# Analog_Front_End.net
KiCad netlist of a schematic drawn in Altium Designer
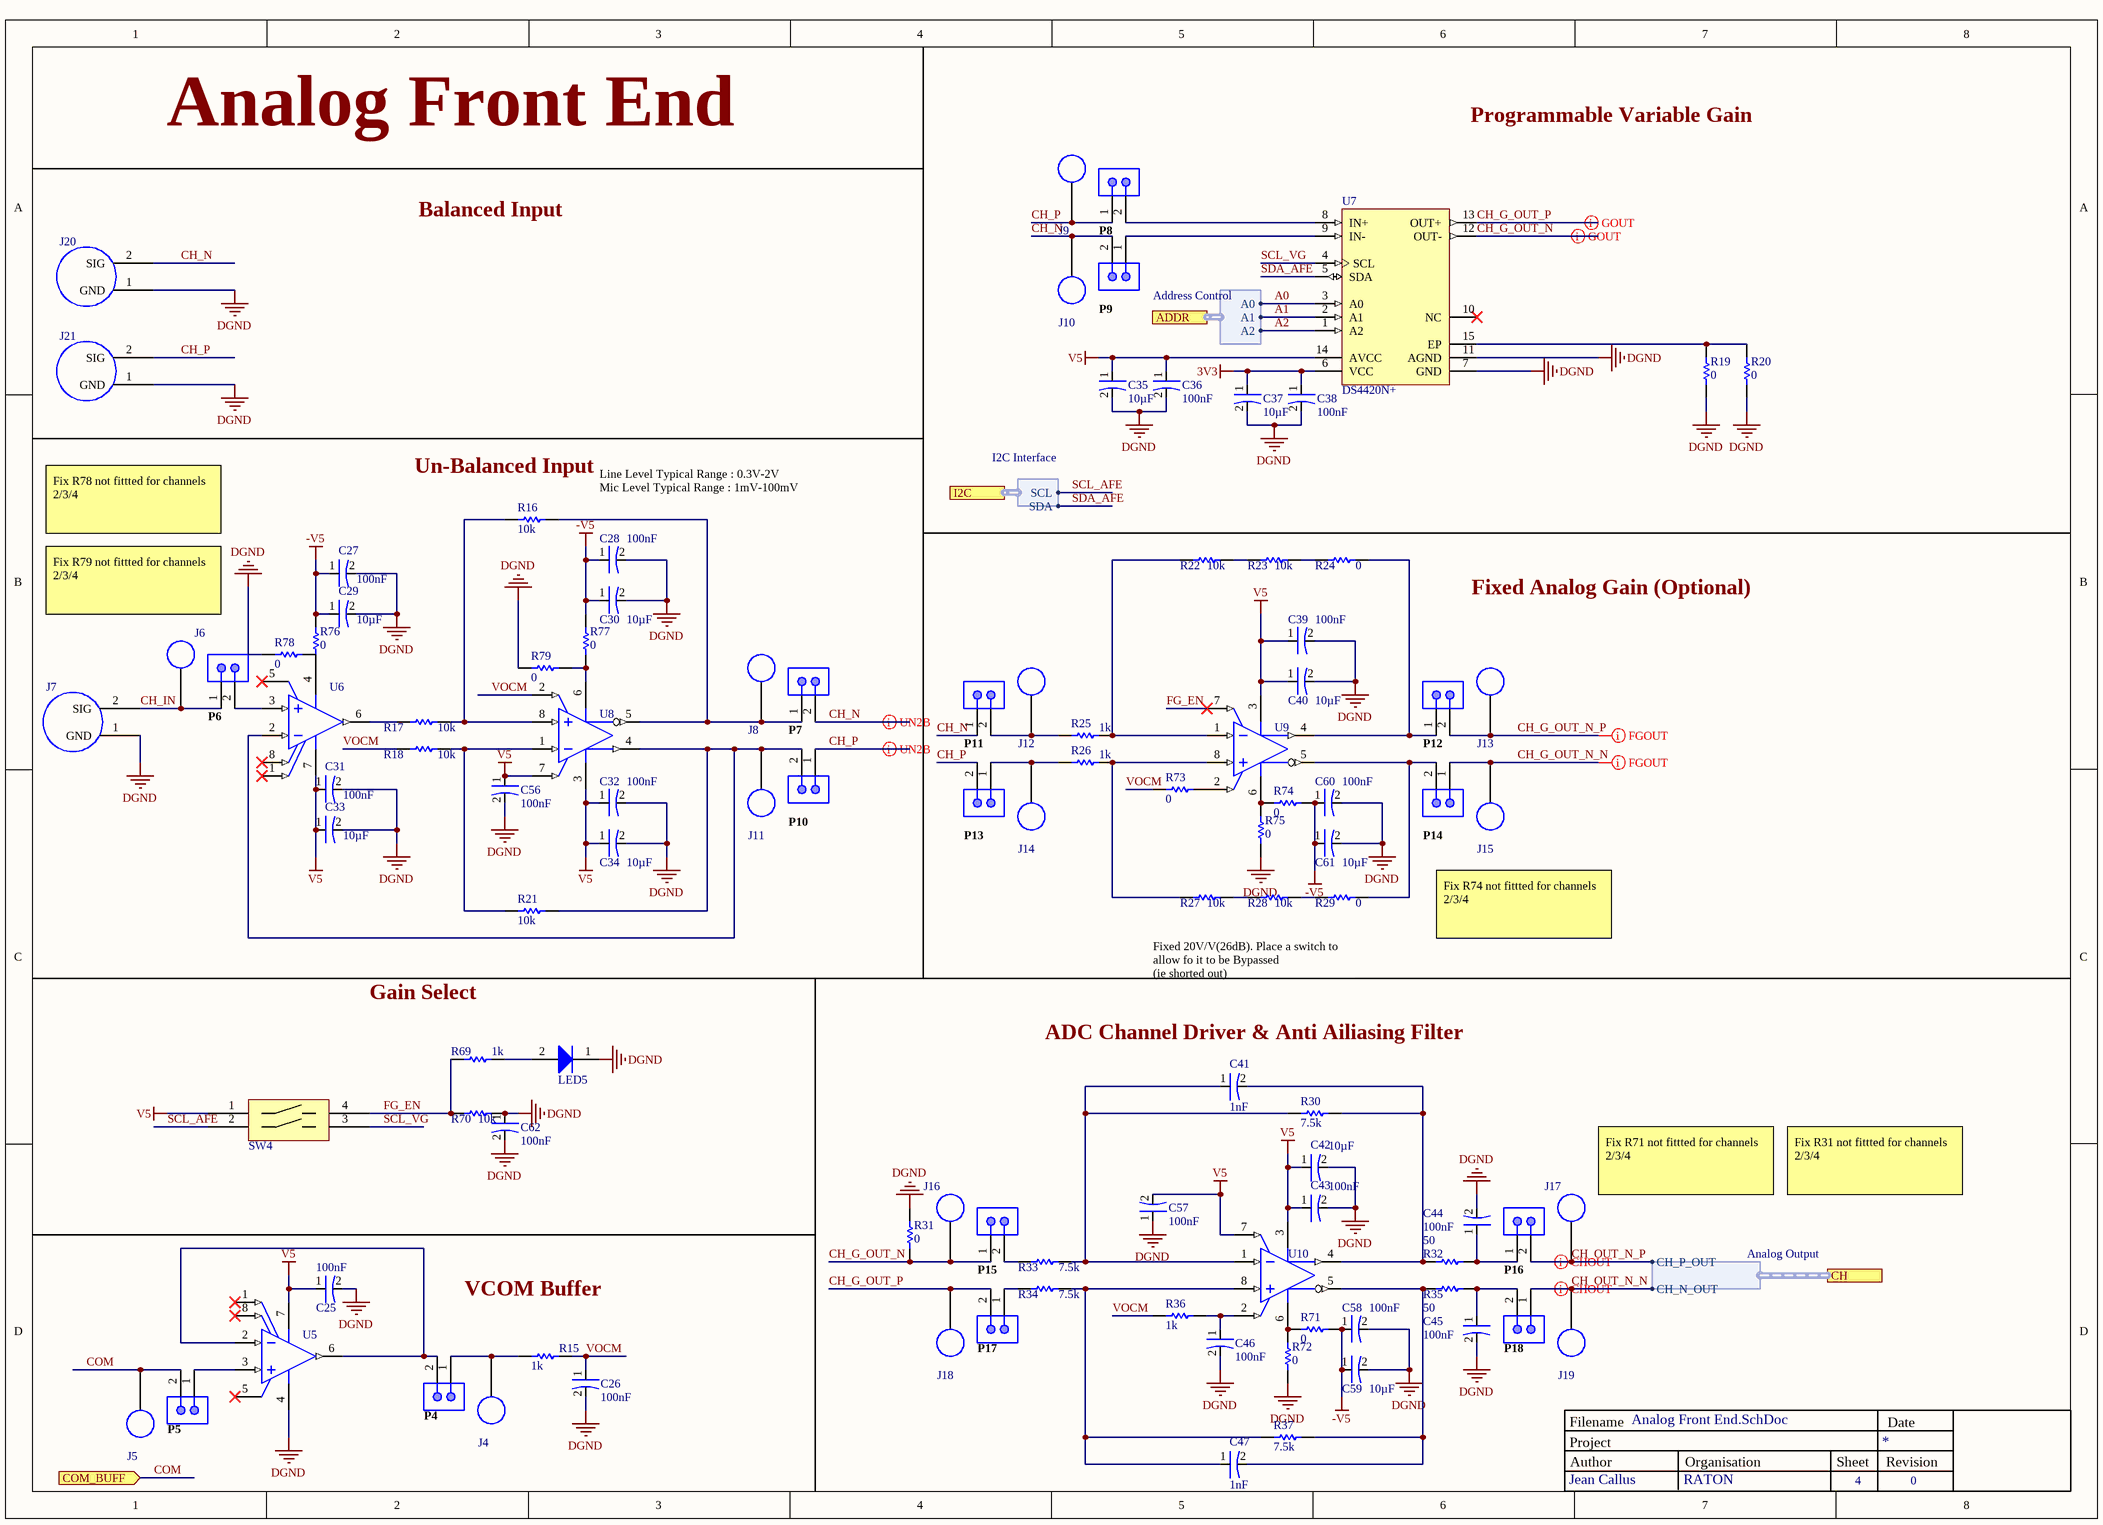
[diagram p0: Analog Front End.SchDoc]

(export (version "E")
  (design (tool "Eeschema 10.0.6"))
  (components
    (comp (ref "C25")
      (value "100nF")
      (footprint "0805-M")
      (description "CAP-0.1uF-CER-0805-50V- X7R-5%")
      (fields
        (field (name "MANUFACTURER") "Generic")
        (field (name "Comment") "CAP 0.1uF CER 0805 50V  X7R 5%")
      )
      (libsource (lib "") (part "Symbol_1"))
    )
    (comp (ref "C26")
      (value "100nF")
      (footprint "0805-M")
      (description "CAP-0.1uF-CER-0805-50V- X7R-5%")
      (fields
        (field (name "MANUFACTURER") "Generic")
        (field (name "Comment") "CAP 0.1uF CER 0805 50V  X7R 5%")
      )
      (libsource (lib "") (part "Symbol_1"))
    )
    (comp (ref "C27")
      (value "100nF")
      (footprint "0805-M")
      (description "CAP-0.1uF-CER-0805-50V- X7R-5%")
      (fields
        (field (name "MANUFACTURER") "Generic")
        (field (name "Comment") "CAP 0.1uF CER 0805 50V  X7R 5%")
      )
      (libsource (lib "") (part "Symbol_2"))
    )
    (comp (ref "C28")
      (value "100nF")
      (footprint "0805-M")
      (description "CAP-0.1uF-CER-0805-50V- X7R-5%")
      (fields
        (field (name "MANUFACTURER") "Generic")
        (field (name "Comment") "CAP 0.1uF CER 0805 50V  X7R 5%")
      )
      (libsource (lib "") (part "Symbol_2"))
    )
    (comp (ref "C29")
      (value "10µF")
      (footprint "0805-M")
      (description "CAP-10uF-CER-0805-25V-X5R-10%")
      (fields
        (field (name "MANUFACTURER") "Generic")
        (field (name "Comment") "CAP 10uF CER 0805 25V X5R 10%")
      )
      (libsource (lib "") (part "Symbol_2"))
    )
    (comp (ref "C30")
      (value "10µF")
      (footprint "0805-M")
      (description "CAP-10uF-CER-0805-25V-X5R-10%")
      (fields
        (field (name "MANUFACTURER") "Generic")
        (field (name "Comment") "CAP 10uF CER 0805 25V X5R 10%")
      )
      (libsource (lib "") (part "Symbol_2"))
    )
    (comp (ref "C31")
      (value "100nF")
      (footprint "0805-M")
      (description "CAP-0.1uF-CER-0805-50V- X7R-5%")
      (fields
        (field (name "MANUFACTURER") "Generic")
        (field (name "Comment") "CAP 0.1uF CER 0805 50V  X7R 5%")
      )
      (libsource (lib "") (part "Symbol_2"))
    )
    (comp (ref "C32")
      (value "100nF")
      (footprint "0805-M")
      (description "CAP-0.1uF-CER-0805-50V- X7R-5%")
      (fields
        (field (name "MANUFACTURER") "Generic")
        (field (name "Comment") "CAP 0.1uF CER 0805 50V  X7R 5%")
      )
      (libsource (lib "") (part "Symbol_2"))
    )
    (comp (ref "C33")
      (value "10µF")
      (footprint "0805-M")
      (description "CAP-10uF-CER-0805-25V-X5R-10%")
      (fields
        (field (name "MANUFACTURER") "Generic")
        (field (name "Comment") "CAP 10uF CER 0805 25V X5R 10%")
      )
      (libsource (lib "") (part "Symbol_2"))
    )
    (comp (ref "C34")
      (value "10µF")
      (footprint "0805-M")
      (description "CAP-10uF-CER-0805-25V-X5R-10%")
      (fields
        (field (name "MANUFACTURER") "Generic")
        (field (name "Comment") "CAP 10uF CER 0805 25V X5R 10%")
      )
      (libsource (lib "") (part "Symbol_2"))
    )
    (comp (ref "C35")
      (value "10µF")
      (footprint "0805-M")
      (description "CAP-10uF-CER-0805-25V-X5R-10%")
      (fields
        (field (name "MANUFACTURER") "Generic")
        (field (name "Comment") "CAP 10uF CER 0805 25V X5R 10%")
      )
      (libsource (lib "") (part "Symbol_2"))
    )
    (comp (ref "C36")
      (value "100nF")
      (footprint "0805-M")
      (description "CAP-0.1uF-CER-0805-50V- X7R-5%")
      (fields
        (field (name "MANUFACTURER") "Generic")
        (field (name "Comment") "CAP 0.1uF CER 0805 50V  X7R 5%")
      )
      (libsource (lib "") (part "Symbol_2"))
    )
    (comp (ref "C37")
      (value "10µF")
      (footprint "0805-M")
      (description "CAP-10uF-CER-0805-25V-X5R-10%")
      (fields
        (field (name "MANUFACTURER") "Generic")
        (field (name "Comment") "CAP 10uF CER 0805 25V X5R 10%")
      )
      (libsource (lib "") (part "Symbol_2"))
    )
    (comp (ref "C38")
      (value "100nF")
      (footprint "0805-M")
      (description "CAP-0.1uF-CER-0805-50V- X7R-5%")
      (fields
        (field (name "MANUFACTURER") "Generic")
        (field (name "Comment") "CAP 0.1uF CER 0805 50V  X7R 5%")
      )
      (libsource (lib "") (part "Symbol_2"))
    )
    (comp (ref "C39")
      (value "100nF")
      (footprint "0805-M")
      (description "CAP-0.1uF-CER-0805-50V- X7R-5%")
      (fields
        (field (name "MANUFACTURER") "Generic")
        (field (name "Comment") "CAP 0.1uF CER 0805 50V  X7R 5%")
      )
      (libsource (lib "") (part "Symbol_2"))
    )
    (comp (ref "C40")
      (value "10µF")
      (footprint "0805-M")
      (description "CAP-10uF-CER-0805-25V-X5R-10%")
      (fields
        (field (name "MANUFACTURER") "Generic")
        (field (name "Comment") "CAP 10uF CER 0805 25V X5R 10%")
      )
      (libsource (lib "") (part "Symbol_2"))
    )
    (comp (ref "C41")
      (value "1nF")
      (footprint "0805-M")
      (description "CAP 1nF CER 0805 25V X7R 5%")
      (fields (field (name "MANUFACTURER") "Generic"))
      (libsource (lib "") (part "Symbol_1"))
    )
    (comp (ref "C42")
      (value "10µF")
      (footprint "0805-M")
      (description "CAP-10uF-CER-0805-25V-X5R-10%")
      (fields
        (field (name "MANUFACTURER") "Generic")
        (field (name "Comment") "CAP 10uF CER 0805 25V X5R 10%")
      )
      (libsource (lib "") (part "Symbol_1"))
    )
    (comp (ref "C43")
      (value "100nF")
      (footprint "0805-M")
      (description "CAP-0.1uF-CER-0805-50V- X7R-5%")
      (fields
        (field (name "MANUFACTURER") "Generic")
        (field (name "Comment") "CAP 0.1uF CER 0805 50V  X7R 5%")
      )
      (libsource (lib "") (part "Symbol_1"))
    )
    (comp (ref "C44")
      (value "100nF")
      (footprint "0805-M")
      (description "CAP-0.1uF-CER-0805-50V- X7R-5%")
      (fields
        (field (name "MANUFACTURER") "Generic")
        (field (name "Comment") "CAP 0.1uF CER 0805 50V  X7R 5%")
      )
      (libsource (lib "") (part "Symbol_1"))
    )
    (comp (ref "C45")
      (value "100nF")
      (footprint "0805-M")
      (description "CAP-0.1uF-CER-0805-50V- X7R-5%")
      (fields
        (field (name "MANUFACTURER") "Generic")
        (field (name "Comment") "CAP 0.1uF CER 0805 50V  X7R 5%")
      )
      (libsource (lib "") (part "Symbol_1"))
    )
    (comp (ref "C46")
      (value "100nF")
      (footprint "0805-M")
      (description "CAP-0.1uF-CER-0805-50V- X7R-5%")
      (fields
        (field (name "MANUFACTURER") "Generic")
        (field (name "Comment") "CAP 0.1uF CER 0805 50V  X7R 5%")
      )
      (libsource (lib "") (part "Symbol_1"))
    )
    (comp (ref "C47")
      (value "1nF")
      (footprint "0805-M")
      (description "CAP 1nF CER 0805 25V X7R 5%")
      (fields (field (name "MANUFACTURER") "Generic"))
      (libsource (lib "") (part "Symbol_1"))
    )
    (comp (ref "C56")
      (value "100nF")
      (footprint "0805-M")
      (description "CAP-0.1uF-CER-0805-50V- X7R-5%")
      (fields
        (field (name "MANUFACTURER") "Generic")
        (field (name "Comment") "CAP 0.1uF CER 0805 50V  X7R 5%")
      )
      (libsource (lib "") (part "Symbol_2"))
    )
    (comp (ref "C57")
      (value "100nF")
      (footprint "0805-M")
      (description "CAP-0.1uF-CER-0805-50V- X7R-5%")
      (fields
        (field (name "MANUFACTURER") "Generic")
        (field (name "Comment") "CAP 0.1uF CER 0805 50V  X7R 5%")
      )
      (libsource (lib "") (part "Symbol_1"))
    )
    (comp (ref "C58")
      (value "100nF")
      (footprint "0805-M")
      (description "CAP-0.1uF-CER-0805-50V- X7R-5%")
      (fields
        (field (name "MANUFACTURER") "Generic")
        (field (name "Comment") "CAP 0.1uF CER 0805 50V  X7R 5%")
      )
      (libsource (lib "") (part "Symbol_2"))
    )
    (comp (ref "C59")
      (value "10µF")
      (footprint "0805-M")
      (description "CAP-10uF-CER-0805-25V-X5R-10%")
      (fields
        (field (name "MANUFACTURER") "Generic")
        (field (name "Comment") "CAP 10uF CER 0805 25V X5R 10%")
      )
      (libsource (lib "") (part "Symbol_2"))
    )
    (comp (ref "C60")
      (value "100nF")
      (footprint "0805-M")
      (description "CAP-0.1uF-CER-0805-50V- X7R-5%")
      (fields
        (field (name "MANUFACTURER") "Generic")
        (field (name "Comment") "CAP 0.1uF CER 0805 50V  X7R 5%")
      )
      (libsource (lib "") (part "Symbol_2"))
    )
    (comp (ref "C61")
      (value "10µF")
      (footprint "0805-M")
      (description "CAP-10uF-CER-0805-25V-X5R-10%")
      (fields
        (field (name "MANUFACTURER") "Generic")
        (field (name "Comment") "CAP 10uF CER 0805 25V X5R 10%")
      )
      (libsource (lib "") (part "Symbol_2"))
    )
    (comp (ref "C62")
      (value "100nF")
      (footprint "0805-M")
      (description "CAP-0.1uF-CER-0805-50V- X7R-5%")
      (fields
        (field (name "MANUFACTURER") "Generic")
        (field (name "Comment") "CAP 0.1uF CER 0805 50V  X7R 5%")
      )
      (libsource (lib "") (part "Symbol_2"))
    )
    (comp (ref "J4")
      (value "151-203-RC")
      (footprint "151-203-RC-Footprint-1")
      (description "PCB-Probe-Ring")
      (libsource (lib "University of Malta - MEMENTO") (part "PCB Probe Ring"))
    )
    (comp (ref "J5")
      (value "151-203-RC")
      (footprint "151-203-RC-Footprint-1")
      (description "PCB-Probe-Ring")
      (libsource (lib "University of Malta - MEMENTO") (part "PCB Probe Ring"))
    )
    (comp (ref "J6")
      (value "151-203-RC")
      (footprint "151-203-RC-Footprint-1")
      (description "PCB-Probe-Ring")
      (libsource (lib "University of Malta - MEMENTO") (part "PCB Probe Ring"))
    )
    (comp (ref "J7")
      (value "SMA CONNECTOR")
      (footprint "SMA CONNECTOR-Footprint-1")
      (fields (field (name "MANUFACTURER") "LPRS"))
      (libsource (lib "University of Malta - MEMENTO") (part "SMA CONNECTOR"))
    )
    (comp (ref "J8")
      (value "151-203-RC")
      (footprint "151-203-RC-Footprint-1")
      (description "PCB-Probe-Ring")
      (libsource (lib "University of Malta - MEMENTO") (part "PCB Probe Ring"))
    )
    (comp (ref "J9")
      (value "151-203-RC")
      (footprint "151-203-RC-Footprint-1")
      (description "PCB-Probe-Ring")
      (libsource (lib "University of Malta - MEMENTO") (part "PCB Probe Ring"))
    )
    (comp (ref "J10")
      (value "151-203-RC")
      (footprint "151-203-RC-Footprint-1")
      (description "PCB-Probe-Ring")
      (libsource (lib "University of Malta - MEMENTO") (part "PCB Probe Ring"))
    )
    (comp (ref "J11")
      (value "151-203-RC")
      (footprint "151-203-RC-Footprint-1")
      (description "PCB-Probe-Ring")
      (libsource (lib "University of Malta - MEMENTO") (part "PCB Probe Ring"))
    )
    (comp (ref "J12")
      (value "151-203-RC")
      (footprint "151-203-RC-Footprint-1")
      (description "PCB-Probe-Ring")
      (libsource (lib "University of Malta - MEMENTO") (part "PCB Probe Ring"))
    )
    (comp (ref "J13")
      (value "151-203-RC")
      (footprint "151-203-RC-Footprint-1")
      (description "PCB-Probe-Ring")
      (libsource (lib "University of Malta - MEMENTO") (part "PCB Probe Ring"))
    )
    (comp (ref "J14")
      (value "151-203-RC")
      (footprint "151-203-RC-Footprint-1")
      (description "PCB-Probe-Ring")
      (libsource (lib "University of Malta - MEMENTO") (part "PCB Probe Ring"))
    )
    (comp (ref "J15")
      (value "151-203-RC")
      (footprint "151-203-RC-Footprint-1")
      (description "PCB-Probe-Ring")
      (libsource (lib "University of Malta - MEMENTO") (part "PCB Probe Ring"))
    )
    (comp (ref "J16")
      (value "151-203-RC")
      (footprint "151-203-RC-Footprint-1")
      (description "PCB-Probe-Ring")
      (libsource (lib "University of Malta - MEMENTO") (part "PCB Probe Ring"))
    )
    (comp (ref "J17")
      (value "151-203-RC")
      (footprint "151-203-RC-Footprint-1")
      (description "PCB-Probe-Ring")
      (libsource (lib "University of Malta - MEMENTO") (part "PCB Probe Ring"))
    )
    (comp (ref "J18")
      (value "151-203-RC")
      (footprint "151-203-RC-Footprint-1")
      (description "PCB-Probe-Ring")
      (libsource (lib "University of Malta - MEMENTO") (part "PCB Probe Ring"))
    )
    (comp (ref "J19")
      (value "151-203-RC")
      (footprint "151-203-RC-Footprint-1")
      (description "PCB-Probe-Ring")
      (libsource (lib "University of Malta - MEMENTO") (part "PCB Probe Ring"))
    )
    (comp (ref "J20")
      (value "SMA CONNECTOR")
      (footprint "SMA CONNECTOR-Footprint-1")
      (fields (field (name "MANUFACTURER") "LPRS"))
      (libsource (lib "University of Malta - MEMENTO") (part "SMA CONNECTOR"))
    )
    (comp (ref "J21")
      (value "SMA CONNECTOR")
      (footprint "SMA CONNECTOR-Footprint-1")
      (fields (field (name "MANUFACTURER") "LPRS"))
      (libsource (lib "University of Malta - MEMENTO") (part "SMA CONNECTOR"))
    )
    (comp (ref "LED5")
      (value "LED 0603 Red 20mA 1.7V")
      (footprint "0603 Generic")
      (description "LED-0603-Red-20mA-1.7V-STOCK")
      (fields (field (name "MANUFACTURER") "Generic"))
      (libsource (lib "") (part "Symbol_3"))
    )
    (comp (ref "P4")
      (value "GENERIC 2PIN HEADER MALE")
      (footprint "GENERIC 2PIN HEADER 0")
      (description "CONN MAL TH 2 0Deg HEADER")
      (fields (field (name "MANUFACTURER") "Generic"))
      (libsource (lib "University of Malta - MEMENTO") (part "GENERIC 2PIN HEADER MALE"))
    )
    (comp (ref "P5")
      (value "GENERIC 2PIN HEADER MALE")
      (footprint "GENERIC 2PIN HEADER 0")
      (description "CONN MAL TH 2 0Deg HEADER")
      (fields (field (name "MANUFACTURER") "Generic"))
      (libsource (lib "University of Malta - MEMENTO") (part "GENERIC 2PIN HEADER MALE"))
    )
    (comp (ref "P6")
      (value "GENERIC 2PIN HEADER MALE")
      (footprint "GENERIC 2PIN HEADER 0")
      (description "CONN MAL TH 2 0Deg HEADER")
      (fields (field (name "MANUFACTURER") "Generic"))
      (libsource (lib "") (part "GENERIC 2PIN HEADER MALE_1"))
    )
    (comp (ref "P7")
      (value "GENERIC 2PIN HEADER MALE")
      (footprint "GENERIC 2PIN HEADER 0")
      (description "CONN MAL TH 2 0Deg HEADER")
      (fields (field (name "MANUFACTURER") "Generic"))
      (libsource (lib "") (part "GENERIC 2PIN HEADER MALE_1"))
    )
    (comp (ref "P8")
      (value "GENERIC 2PIN HEADER MALE")
      (footprint "GENERIC 2PIN HEADER 0")
      (description "CONN MAL TH 2 0Deg HEADER")
      (fields (field (name "MANUFACTURER") "Generic"))
      (libsource (lib "") (part "GENERIC 2PIN HEADER MALE_1"))
    )
    (comp (ref "P9")
      (value "GENERIC 2PIN HEADER MALE")
      (footprint "GENERIC 2PIN HEADER 0")
      (description "CONN MAL TH 2 0Deg HEADER")
      (fields (field (name "MANUFACTURER") "Generic"))
      (libsource (lib "University of Malta - MEMENTO") (part "GENERIC 2PIN HEADER MALE"))
    )
    (comp (ref "P10")
      (value "GENERIC 2PIN HEADER MALE")
      (footprint "GENERIC 2PIN HEADER 0")
      (description "CONN MAL TH 2 0Deg HEADER")
      (fields (field (name "MANUFACTURER") "Generic"))
      (libsource (lib "University of Malta - MEMENTO") (part "GENERIC 2PIN HEADER MALE"))
    )
    (comp (ref "P11")
      (value "GENERIC 2PIN HEADER MALE")
      (footprint "GENERIC 2PIN HEADER 0")
      (description "CONN MAL TH 2 0Deg HEADER")
      (fields (field (name "MANUFACTURER") "Generic"))
      (libsource (lib "") (part "GENERIC 2PIN HEADER MALE_1"))
    )
    (comp (ref "P12")
      (value "GENERIC 2PIN HEADER MALE")
      (footprint "GENERIC 2PIN HEADER 0")
      (description "CONN MAL TH 2 0Deg HEADER")
      (fields (field (name "MANUFACTURER") "Generic"))
      (libsource (lib "") (part "GENERIC 2PIN HEADER MALE_1"))
    )
    (comp (ref "P13")
      (value "GENERIC 2PIN HEADER MALE")
      (footprint "GENERIC 2PIN HEADER 0")
      (description "CONN MAL TH 2 0Deg HEADER")
      (fields (field (name "MANUFACTURER") "Generic"))
      (libsource (lib "University of Malta - MEMENTO") (part "GENERIC 2PIN HEADER MALE"))
    )
    (comp (ref "P14")
      (value "GENERIC 2PIN HEADER MALE")
      (footprint "GENERIC 2PIN HEADER 0")
      (description "CONN MAL TH 2 0Deg HEADER")
      (fields (field (name "MANUFACTURER") "Generic"))
      (libsource (lib "University of Malta - MEMENTO") (part "GENERIC 2PIN HEADER MALE"))
    )
    (comp (ref "P15")
      (value "GENERIC 2PIN HEADER MALE")
      (footprint "GENERIC 2PIN HEADER 0")
      (description "CONN MAL TH 2 0Deg HEADER")
      (fields (field (name "MANUFACTURER") "Generic"))
      (libsource (lib "") (part "GENERIC 2PIN HEADER MALE_1"))
    )
    (comp (ref "P16")
      (value "GENERIC 2PIN HEADER MALE")
      (footprint "GENERIC 2PIN HEADER 0")
      (description "CONN MAL TH 2 0Deg HEADER")
      (fields (field (name "MANUFACTURER") "Generic"))
      (libsource (lib "") (part "GENERIC 2PIN HEADER MALE_1"))
    )
    (comp (ref "P17")
      (value "GENERIC 2PIN HEADER MALE")
      (footprint "GENERIC 2PIN HEADER 0")
      (description "CONN MAL TH 2 0Deg HEADER")
      (fields (field (name "MANUFACTURER") "Generic"))
      (libsource (lib "University of Malta - MEMENTO") (part "GENERIC 2PIN HEADER MALE"))
    )
    (comp (ref "P18")
      (value "GENERIC 2PIN HEADER MALE")
      (footprint "GENERIC 2PIN HEADER 0")
      (description "CONN MAL TH 2 0Deg HEADER")
      (fields (field (name "MANUFACTURER") "Generic"))
      (libsource (lib "University of Malta - MEMENTO") (part "GENERIC 2PIN HEADER MALE"))
    )
    (comp (ref "R15")
      (value "1k")
      (footprint "0805-M")
      (description "RES-1k-0805-125mW-5%")
      (fields (field (name "MANUFACTURER") "Generic") (field (name "Comment") "RES 1k 0805 125mW 5%"))
      (libsource (lib "University of Malta - MEMENTO") (part "Symbol"))
    )
    (comp (ref "R16")
      (value "10k")
      (footprint "0402-M")
      (description "RES-10k-0402-63mW-5%")
      (fields (field (name "MANUFACTURER") "Generic") (field (name "Comment") "RES 10k 0402 63mW 5%"))
      (libsource (lib "University of Malta - MEMENTO") (part "Symbol"))
    )
    (comp (ref "R17")
      (value "10k")
      (footprint "0402-M")
      (description "RES-10k-0402-63mW-5%")
      (fields (field (name "MANUFACTURER") "Generic") (field (name "Comment") "RES 10k 0402 63mW 5%"))
      (libsource (lib "University of Malta - MEMENTO") (part "Symbol"))
    )
    (comp (ref "R18")
      (value "10k")
      (footprint "0402-M")
      (description "RES-10k-0402-63mW-5%")
      (fields (field (name "MANUFACTURER") "Generic") (field (name "Comment") "RES 10k 0402 63mW 5%"))
      (libsource (lib "University of Malta - MEMENTO") (part "Symbol"))
    )
    (comp (ref "R19")
      (value "0")
      (footprint "0402-M")
      (description "RES-0-0402-63mW-5%")
      (fields (field (name "MANUFACTURER") "Generic") (field (name "Comment") "RES 0 0402 63mW"))
      (libsource (lib "University of Malta - MEMENTO") (part "Symbol"))
    )
    (comp (ref "R20")
      (value "0")
      (footprint "0402-M")
      (description "RES-0-0402-63mW-5%")
      (fields (field (name "MANUFACTURER") "Generic") (field (name "Comment") "RES 0 0402 63mW"))
      (libsource (lib "University of Malta - MEMENTO") (part "Symbol"))
    )
    (comp (ref "R21")
      (value "10k")
      (footprint "0402-M")
      (description "RES-10k-0402-63mW-5%")
      (fields (field (name "MANUFACTURER") "Generic") (field (name "Comment") "RES 10k 0402 63mW 5%"))
      (libsource (lib "University of Malta - MEMENTO") (part "Symbol"))
    )
    (comp (ref "R22")
      (value "10k")
      (footprint "0805-M")
      (description "RES-10k-0805-125mW-1%")
      (fields (field (name "MANUFACTURER") "Generic") (field (name "Comment") "RES 10k 0805 125mW 1%"))
      (libsource (lib "University of Malta - MEMENTO") (part "Symbol"))
    )
    (comp (ref "R23")
      (value "10k")
      (footprint "0805-M")
      (description "RES-10k-0805-125mW-1%")
      (fields (field (name "MANUFACTURER") "Generic") (field (name "Comment") "RES 10k 0805 125mW 1%"))
      (libsource (lib "University of Malta - MEMENTO") (part "Symbol"))
    )
    (comp (ref "R24")
      (value "0")
      (footprint "0402-M")
      (description "RES-0-0402-63mW-5%")
      (fields (field (name "MANUFACTURER") "Generic") (field (name "Comment") "RES 0 0402 63mW"))
      (libsource (lib "University of Malta - MEMENTO") (part "Symbol"))
    )
    (comp (ref "R25")
      (value "1k")
      (footprint "0805-M")
      (description "RES-1k-0805-125mW-5%")
      (fields (field (name "MANUFACTURER") "Generic") (field (name "Comment") "RES 1k 0805 125mW 5%"))
      (libsource (lib "University of Malta - MEMENTO") (part "Symbol"))
    )
    (comp (ref "R26")
      (value "1k")
      (footprint "0805-M")
      (description "RES-1k-0805-125mW-5%")
      (fields (field (name "MANUFACTURER") "Generic") (field (name "Comment") "RES 1k 0805 125mW 5%"))
      (libsource (lib "University of Malta - MEMENTO") (part "Symbol"))
    )
    (comp (ref "R27")
      (value "10k")
      (footprint "0805-M")
      (description "RES-10k-0805-125mW-1%")
      (fields (field (name "MANUFACTURER") "Generic") (field (name "Comment") "RES 10k 0805 125mW 1%"))
      (libsource (lib "University of Malta - MEMENTO") (part "Symbol"))
    )
    (comp (ref "R28")
      (value "10k")
      (footprint "0805-M")
      (description "RES-10k-0805-125mW-1%")
      (fields (field (name "MANUFACTURER") "Generic") (field (name "Comment") "RES 10k 0805 125mW 1%"))
      (libsource (lib "University of Malta - MEMENTO") (part "Symbol"))
    )
    (comp (ref "R29")
      (value "0")
      (footprint "0402-M")
      (description "RES-0-0402-63mW-5%")
      (fields (field (name "MANUFACTURER") "Generic") (field (name "Comment") "RES 0 0402 63mW"))
      (libsource (lib "University of Malta - MEMENTO") (part "Symbol"))
    )
    (comp (ref "R30")
      (value "7.5k")
      (footprint "0402-M")
      (description "RES-7.5k-0402-63mW-5%")
      (fields (field (name "MANUFACTURER") "Generic") (field (name "Comment") "RES 7.5k 0402 63mW 5%"))
      (libsource (lib "University of Malta - MEMENTO") (part "Symbol"))
    )
    (comp (ref "R31")
      (value "0")
      (footprint "0402-M")
      (description "RES-0-0402-63mW-5%")
      (fields (field (name "MANUFACTURER") "Generic") (field (name "Comment") "RES 0 0402 63mW"))
      (libsource (lib "University of Malta - MEMENTO") (part "Symbol"))
    )
    (comp (ref "R32")
      (value "50")
      (footprint "0805-L")
      (description "RES-50-0805-125mW-1%")
      (fields (field (name "MANUFACTURER") "Generic") (field (name "Comment") "RES 50 0805 125mW 1%"))
      (libsource (lib "University of Malta - MEMENTO") (part "Symbol"))
    )
    (comp (ref "R33")
      (value "7.5k")
      (footprint "0402-M")
      (description "RES-7.5k-0402-63mW-5%")
      (fields (field (name "MANUFACTURER") "Generic") (field (name "Comment") "RES 7.5k 0402 63mW 5%"))
      (libsource (lib "University of Malta - MEMENTO") (part "Symbol"))
    )
    (comp (ref "R34")
      (value "7.5k")
      (footprint "0402-M")
      (description "RES-7.5k-0402-63mW-5%")
      (fields (field (name "MANUFACTURER") "Generic") (field (name "Comment") "RES 7.5k 0402 63mW 5%"))
      (libsource (lib "University of Malta - MEMENTO") (part "Symbol"))
    )
    (comp (ref "R35")
      (value "50")
      (footprint "0805-L")
      (description "RES-50-0805-125mW-1%")
      (fields (field (name "MANUFACTURER") "Generic") (field (name "Comment") "RES 50 0805 125mW 1%"))
      (libsource (lib "University of Malta - MEMENTO") (part "Symbol"))
    )
    (comp (ref "R36")
      (value "1k")
      (footprint "0805-M")
      (description "RES-1k-0805-125mW-5%")
      (fields (field (name "MANUFACTURER") "Generic") (field (name "Comment") "RES 1k 0805 125mW 5%"))
      (libsource (lib "University of Malta - MEMENTO") (part "Symbol"))
    )
    (comp (ref "R37")
      (value "7.5k")
      (footprint "0402-M")
      (description "RES-7.5k-0402-63mW-5%")
      (fields (field (name "MANUFACTURER") "Generic") (field (name "Comment") "RES 7.5k 0402 63mW 5%"))
      (libsource (lib "University of Malta - MEMENTO") (part "Symbol"))
    )
    (comp (ref "R69")
      (value "1k")
      (footprint "0805-M")
      (description "RES-1k-0805-125mW-5%")
      (fields (field (name "MANUFACTURER") "Generic") (field (name "Comment") "RES 1k 0805 125mW 5%"))
      (libsource (lib "University of Malta - MEMENTO") (part "Symbol"))
    )
    (comp (ref "R70")
      (value "10k")
      (footprint "0805-M")
      (description "RES-10k-0805-125mW-1%")
      (fields (field (name "MANUFACTURER") "Generic") (field (name "Comment") "RES 10k 0805 125mW 1%"))
      (libsource (lib "University of Malta - MEMENTO") (part "Symbol"))
    )
    (comp (ref "R71")
      (value "0")
      (footprint "0402-M")
      (description "RES-0-0402-63mW-5%")
      (fields (field (name "MANUFACTURER") "Generic") (field (name "Comment") "RES 0 0402 63mW"))
      (libsource (lib "University of Malta - MEMENTO") (part "Symbol"))
    )
    (comp (ref "R72")
      (value "0")
      (footprint "0402-M")
      (description "RES-0-0402-63mW-5%")
      (fields (field (name "MANUFACTURER") "Generic") (field (name "Comment") "RES 0 0402 63mW"))
      (libsource (lib "University of Malta - MEMENTO") (part "Symbol"))
    )
    (comp (ref "R73")
      (value "0")
      (footprint "0402-M")
      (description "RES-0-0402-63mW-5%")
      (fields (field (name "MANUFACTURER") "Generic") (field (name "Comment") "RES 0 0402 63mW"))
      (libsource (lib "University of Malta - MEMENTO") (part "Symbol"))
    )
    (comp (ref "R74")
      (value "0")
      (footprint "0402-M")
      (description "RES-0-0402-63mW-5%")
      (fields (field (name "MANUFACTURER") "Generic") (field (name "Comment") "RES 0 0402 63mW"))
      (libsource (lib "University of Malta - MEMENTO") (part "Symbol"))
    )
    (comp (ref "R75")
      (value "0")
      (footprint "0402-M")
      (description "RES-0-0402-63mW-5%")
      (fields (field (name "MANUFACTURER") "Generic") (field (name "Comment") "RES 0 0402 63mW"))
      (libsource (lib "University of Malta - MEMENTO") (part "Symbol"))
    )
    (comp (ref "R76")
      (value "0")
      (footprint "0402-M")
      (description "RES-0-0402-63mW-5%")
      (fields (field (name "MANUFACTURER") "Generic") (field (name "Comment") "RES 0 0402 63mW"))
      (libsource (lib "University of Malta - MEMENTO") (part "Symbol"))
    )
    (comp (ref "R77")
      (value "0")
      (footprint "0402-M")
      (description "RES-0-0402-63mW-5%")
      (fields (field (name "MANUFACTURER") "Generic") (field (name "Comment") "RES 0 0402 63mW"))
      (libsource (lib "University of Malta - MEMENTO") (part "Symbol"))
    )
    (comp (ref "R78")
      (value "0")
      (footprint "0402-M")
      (description "RES-0-0402-63mW-5%")
      (fields (field (name "MANUFACTURER") "Generic") (field (name "Comment") "RES 0 0402 63mW"))
      (libsource (lib "University of Malta - MEMENTO") (part "Symbol"))
    )
    (comp (ref "R79")
      (value "0")
      (footprint "0402-M")
      (description "RES-0-0402-63mW-5%")
      (fields (field (name "MANUFACTURER") "Generic") (field (name "Comment") "RES 0 0402 63mW"))
      (libsource (lib "University of Malta - MEMENTO") (part "Symbol"))
    )
    (comp (ref "SW4")
      (value "210-2MS")
      (footprint "210-2MS-Footprint-1")
      (description "SWITCH DIP SPST 2 100mA 50V")
      (libsource (lib "University of Malta - MEMENTO") (part "210-2MS"))
    )
    (comp (ref "U5")
      (value "OPA227UA/2K5")
      (footprint "D0008A_L")
      (description "IC OPAMP GP 8MHZ 8SOIC")
      (libsource (lib "University of Malta - MEMENTO") (part "TI-OPA227-8"))
    )
    (comp (ref "U6")
      (value "OPA227UA/2K5")
      (footprint "D0008A_L")
      (description "IC OPAMP GP 8MHZ 8SOIC")
      (libsource (lib "University of Malta - MEMENTO") (part "TI-OPA227-8"))
    )
    (comp (ref "U7")
      (value "DS4420N+")
      (footprint "QFN50P400X300X75_HS-15N")
      (description "Maxim DS4420N+, Programmable Gain Amplifier 67dB, 14-Pin TDFN")
      (libsource (lib "University of Malta - MEMENTO") (part "DS4420-T1433+1"))
    )
    (comp (ref "U8")
      (value "OPA1632DR")
      (footprint "D0008A_L")
      (description "IC OPAMP AUDIO 180MHZ 8SOIC")
      (libsource (lib "University of Malta - MEMENTO") (part "TI-OPA1632D8"))
    )
    (comp (ref "U9")
      (value "OPA1632DR")
      (footprint "D0008A_L")
      (description "IC OPAMP AUDIO 180MHZ 8SOIC")
      (libsource (lib "University of Malta - MEMENTO") (part "TI-OPA1632D8"))
    )
    (comp (ref "U10")
      (value "OPA1632DR")
      (footprint "D0008A_L")
      (description "IC OPAMP AUDIO 180MHZ 8SOIC")
      (libsource (lib "University of Malta - MEMENTO") (part "TI-OPA1632D8"))
    )
  )
  (nets
    (net (code "7") (name "-V5") (class "Default")
      (node (ref "C27") (pin "1") (pinfunction "Anode_1") (pintype "passive"))
      (node (ref "C28") (pin "1") (pinfunction "Anode_1") (pintype "passive"))
      (node (ref "C29") (pin "1") (pinfunction "Anode_1") (pintype "passive"))
      (node (ref "C30") (pin "1") (pinfunction "Anode_1") (pintype "passive"))
      (node (ref "C58") (pin "1") (pinfunction "Anode_1") (pintype "passive"))
      (node (ref "C59") (pin "1") (pinfunction "Anode_1") (pintype "passive"))
      (node (ref "C60") (pin "1") (pinfunction "Anode_1") (pintype "passive"))
      (node (ref "C61") (pin "1") (pinfunction "Anode_1") (pintype "passive"))
      (node (ref "R71") (pin "2") (pinfunction "2_2") (pintype "passive"))
      (node (ref "R74") (pin "1") (pinfunction "1_1") (pintype "passive"))
      (node (ref "R76") (pin "1") (pinfunction "1_1") (pintype "passive"))
      (node (ref "R77") (pin "2") (pinfunction "2_2") (pintype "passive"))
    )
    (net (code "8") (name "/A0") (class "Default")
      (node (ref "U7") (pin "3") (pinfunction "A0_3") (pintype "input"))
    )
    (net (code "9") (name "/A1") (class "Default")
      (node (ref "U7") (pin "2") (pinfunction "A1_2") (pintype "input"))
    )
    (net (code "10") (name "/A2") (class "Default")
      (node (ref "U7") (pin "1") (pinfunction "A2_1") (pintype "input"))
    )
    (net (code "11") (name "/CH_G_OUT_N") (class "Default")
      (node (ref "J16") (pin "1") (pinfunction "1_1") (pintype "passive"))
      (node (ref "P15") (pin "1") (pinfunction "1_1") (pintype "passive"))
      (node (ref "R31") (pin "2") (pinfunction "2_2") (pintype "passive"))
      (node (ref "U7") (pin "12") (pinfunction "OUT-_12") (pintype "output"))
    )
    (net (code "12") (name "/CH_G_OUT_N_N") (class "Default")
      (node (ref "J15") (pin "1") (pinfunction "1_1") (pintype "passive"))
      (node (ref "P14") (pin "1") (pinfunction "1_1") (pintype "passive"))
    )
    (net (code "13") (name "/CH_G_OUT_N_P") (class "Default")
      (node (ref "J13") (pin "1") (pinfunction "1_1") (pintype "passive"))
      (node (ref "P12") (pin "2") (pinfunction "2_2") (pintype "passive"))
    )
    (net (code "14") (name "/CH_G_OUT_P") (class "Default")
      (node (ref "J18") (pin "1") (pinfunction "1_1") (pintype "passive"))
      (node (ref "P17") (pin "2") (pinfunction "2_2") (pintype "passive"))
      (node (ref "U7") (pin "13") (pinfunction "OUT+_13") (pintype "output"))
    )
    (net (code "15") (name "/CH_IN") (class "Default")
      (node (ref "J6") (pin "1") (pinfunction "1_1") (pintype "passive"))
      (node (ref "J7") (pin "2") (pinfunction "SIG_2") (pintype "passive"))
      (node (ref "P6") (pin "1") (pinfunction "1_1") (pintype "passive"))
    )
    (net (code "16") (name "/CH_N") (class "Default")
      (node (ref "J10") (pin "1") (pinfunction "1_1") (pintype "passive"))
      (node (ref "J20") (pin "2") (pinfunction "SIG_2") (pintype "passive"))
      (node (ref "P11") (pin "1") (pinfunction "1_1") (pintype "passive"))
      (node (ref "P7") (pin "2") (pinfunction "2_2") (pintype "passive"))
      (node (ref "P9") (pin "2") (pinfunction "2_2") (pintype "passive"))
    )
    (net (code "17") (name "/CH_OUT_N_N") (class "Default")
      (node (ref "J19") (pin "1") (pinfunction "1_1") (pintype "passive"))
      (node (ref "P18") (pin "1") (pinfunction "1_1") (pintype "passive"))
    )
    (net (code "18") (name "/CH_OUT_N_P") (class "Default")
      (node (ref "J17") (pin "1") (pinfunction "1_1") (pintype "passive"))
      (node (ref "P16") (pin "2") (pinfunction "2_2") (pintype "passive"))
    )
    (net (code "19") (name "/CH_P") (class "Default")
      (node (ref "J21") (pin "2") (pinfunction "SIG_2") (pintype "passive"))
      (node (ref "J9") (pin "1") (pinfunction "1_1") (pintype "passive"))
      (node (ref "P10") (pin "1") (pinfunction "1_1") (pintype "passive"))
      (node (ref "P13") (pin "2") (pinfunction "2_2") (pintype "passive"))
      (node (ref "P8") (pin "1") (pinfunction "1_1") (pintype "passive"))
    )
    (net (code "20") (name "/COM") (class "Default")
      (node (ref "J5") (pin "1") (pinfunction "1_1") (pintype "passive"))
      (node (ref "P5") (pin "2") (pinfunction "2_2") (pintype "passive"))
    )
    (net (code "21") (name "/FG_EN") (class "Default")
      (node (ref "R69") (pin "1") (pinfunction "1_1") (pintype "passive"))
      (node (ref "R70") (pin "1") (pinfunction "1_1") (pintype "passive"))
      (node (ref "SW4") (pin "4") (pinfunction "4_4") (pintype "passive"))
      (node (ref "U9") (pin "7") (pinfunction "ENABLE_7") (pintype "input"))
    )
    (net (code "22") (name "/SCL_AFE") (class "Default")
      (node (ref "SW4") (pin "2") (pinfunction "2_2") (pintype "passive"))
    )
    (net (code "23") (name "/SCL_VG") (class "Default")
      (node (ref "SW4") (pin "3") (pinfunction "4_3") (pintype "passive"))
      (node (ref "U7") (pin "4") (pinfunction "SCL_4") (pintype "input"))
    )
    (net (code "24") (name "/SDA_AFE") (class "Default")
      (node (ref "U7") (pin "5") (pinfunction "SDA_5") (pintype "bidirectional"))
    )
    (net (code "25") (name "/VOCM") (class "Default")
      (node (ref "C26") (pin "1") (pinfunction "Anode_1") (pintype "passive"))
      (node (ref "R15") (pin "2") (pinfunction "2_2") (pintype "passive"))
      (node (ref "R18") (pin "1") (pinfunction "1_1") (pintype "passive"))
      (node (ref "R36") (pin "1") (pinfunction "1_1") (pintype "passive"))
      (node (ref "R73") (pin "2") (pinfunction "2_2") (pintype "passive"))
      (node (ref "U8") (pin "2") (pinfunction "VOCM_2") (pintype "input"))
    )
    (net (code "29") (name "3V3") (class "Default")
      (node (ref "C37") (pin "1") (pinfunction "Anode_1") (pintype "passive"))
      (node (ref "C38") (pin "1") (pinfunction "Anode_1") (pintype "passive"))
      (node (ref "U7") (pin "6") (pinfunction "VCC_6") (pintype "power_in"))
    )
    (net (code "30") (name "DGND") (class "Default")
      (node (ref "C25") (pin "2") (pinfunction "Cathode_2") (pintype "passive"))
      (node (ref "C26") (pin "2") (pinfunction "Cathode_2") (pintype "passive"))
      (node (ref "C27") (pin "2") (pinfunction "Cathode_2") (pintype "passive"))
      (node (ref "C28") (pin "2") (pinfunction "Cathode_2") (pintype "passive"))
      (node (ref "C29") (pin "2") (pinfunction "Cathode_2") (pintype "passive"))
      (node (ref "C30") (pin "2") (pinfunction "Cathode_2") (pintype "passive"))
      (node (ref "C31") (pin "2") (pinfunction "Cathode_2") (pintype "passive"))
      (node (ref "C32") (pin "2") (pinfunction "Cathode_2") (pintype "passive"))
      (node (ref "C33") (pin "2") (pinfunction "Cathode_2") (pintype "passive"))
      (node (ref "C34") (pin "2") (pinfunction "Cathode_2") (pintype "passive"))
      (node (ref "C35") (pin "2") (pinfunction "Cathode_2") (pintype "passive"))
      (node (ref "C36") (pin "2") (pinfunction "Cathode_2") (pintype "passive"))
      (node (ref "C37") (pin "2") (pinfunction "Cathode_2") (pintype "passive"))
      (node (ref "C38") (pin "2") (pinfunction "Cathode_2") (pintype "passive"))
      (node (ref "C39") (pin "2") (pinfunction "Cathode_2") (pintype "passive"))
      (node (ref "C40") (pin "2") (pinfunction "Cathode_2") (pintype "passive"))
      (node (ref "C42") (pin "2") (pinfunction "Cathode_2") (pintype "passive"))
      (node (ref "C43") (pin "2") (pinfunction "Cathode_2") (pintype "passive"))
      (node (ref "C44") (pin "2") (pinfunction "Cathode_2") (pintype "passive"))
      (node (ref "C45") (pin "2") (pinfunction "Cathode_2") (pintype "passive"))
      (node (ref "C46") (pin "2") (pinfunction "Cathode_2") (pintype "passive"))
      (node (ref "C56") (pin "2") (pinfunction "Cathode_2") (pintype "passive"))
      (node (ref "C57") (pin "1") (pinfunction "Anode_1") (pintype "passive"))
      (node (ref "C58") (pin "2") (pinfunction "Cathode_2") (pintype "passive"))
      (node (ref "C59") (pin "2") (pinfunction "Cathode_2") (pintype "passive"))
      (node (ref "C60") (pin "2") (pinfunction "Cathode_2") (pintype "passive"))
      (node (ref "C61") (pin "2") (pinfunction "Cathode_2") (pintype "passive"))
      (node (ref "C62") (pin "1") (pinfunction "Anode_1") (pintype "passive"))
      (node (ref "C62") (pin "2") (pinfunction "Cathode_2") (pintype "passive"))
      (node (ref "J20") (pin "1") (pinfunction "GND_1") (pintype "passive"))
      (node (ref "J21") (pin "1") (pinfunction "GND_1") (pintype "passive"))
      (node (ref "J7") (pin "1") (pinfunction "GND_1") (pintype "passive"))
      (node (ref "LED5") (pin "1") (pinfunction "1_1") (pintype "passive"))
      (node (ref "R19") (pin "1") (pinfunction "1_1") (pintype "passive"))
      (node (ref "R20") (pin "1") (pinfunction "1_1") (pintype "passive"))
      (node (ref "R31") (pin "1") (pinfunction "1_1") (pintype "passive"))
      (node (ref "R70") (pin "2") (pinfunction "2_2") (pintype "passive"))
      (node (ref "R72") (pin "1") (pinfunction "1_1") (pintype "passive"))
      (node (ref "R75") (pin "2") (pinfunction "2_2") (pintype "passive"))
      (node (ref "R78") (pin "1") (pinfunction "1_1") (pintype "passive"))
      (node (ref "R79") (pin "1") (pinfunction "1_1") (pintype "passive"))
      (node (ref "U5") (pin "4") (pinfunction "V-_4") (pintype "power_in"))
      (node (ref "U7") (pin "11") (pinfunction "AGND_11") (pintype "power_in"))
      (node (ref "U7") (pin "7") (pinfunction "GND_7") (pintype "power_in"))
    )
    (net (code "31") (name "Net-(C41-Anode)") (class "Default")
      (node (ref "C41") (pin "1") (pinfunction "Anode_1") (pintype "passive"))
      (node (ref "R30") (pin "1") (pinfunction "1_1") (pintype "passive"))
      (node (ref "R33") (pin "2") (pinfunction "2_2") (pintype "passive"))
      (node (ref "U10") (pin "1") (pinfunction "VIN-_1") (pintype "input"))
    )
    (net (code "32") (name "Net-(C41-Cathode)") (class "Default")
      (node (ref "C41") (pin "2") (pinfunction "Cathode_2") (pintype "passive"))
      (node (ref "R30") (pin "2") (pinfunction "2_2") (pintype "passive"))
      (node (ref "R32") (pin "1") (pinfunction "1_1") (pintype "passive"))
      (node (ref "U10") (pin "4") (pinfunction "VOUT+_4") (pintype "output"))
    )
    (net (code "33") (name "Net-(C44-Anode)") (class "Default")
      (node (ref "C44") (pin "1") (pinfunction "Anode_1") (pintype "passive"))
      (node (ref "P16") (pin "1") (pinfunction "1_1") (pintype "passive"))
      (node (ref "R32") (pin "2") (pinfunction "2_2") (pintype "passive"))
    )
    (net (code "34") (name "Net-(C45-Anode)") (class "Default")
      (node (ref "C45") (pin "1") (pinfunction "Anode_1") (pintype "passive"))
      (node (ref "P18") (pin "2") (pinfunction "2_2") (pintype "passive"))
      (node (ref "R35") (pin "2") (pinfunction "2_2") (pintype "passive"))
    )
    (net (code "35") (name "Net-(C46-Anode)") (class "Default")
      (node (ref "C46") (pin "1") (pinfunction "Anode_1") (pintype "passive"))
      (node (ref "R36") (pin "2") (pinfunction "2_2") (pintype "passive"))
      (node (ref "U10") (pin "2") (pinfunction "VOCM_2") (pintype "input"))
    )
    (net (code "36") (name "Net-(C47-Anode)") (class "Default")
      (node (ref "C47") (pin "1") (pinfunction "Anode_1") (pintype "passive"))
      (node (ref "R34") (pin "2") (pinfunction "2_2") (pintype "passive"))
      (node (ref "R37") (pin "1") (pinfunction "1_1") (pintype "passive"))
      (node (ref "U10") (pin "8") (pinfunction "VIN+_8") (pintype "input"))
    )
    (net (code "37") (name "Net-(C47-Cathode)") (class "Default")
      (node (ref "C47") (pin "2") (pinfunction "Cathode_2") (pintype "passive"))
      (node (ref "R35") (pin "1") (pinfunction "1_1") (pintype "passive"))
      (node (ref "R37") (pin "2") (pinfunction "2_2") (pintype "passive"))
      (node (ref "U10") (pin "5") (pinfunction "VOUT-_5") (pintype "output"))
    )
    (net (code "38") (name "Net-(J4-Pad1)") (class "Default")
      (node (ref "J4") (pin "1") (pinfunction "1_1") (pintype "passive"))
      (node (ref "P4") (pin "1") (pinfunction "1_1") (pintype "passive"))
      (node (ref "R15") (pin "1") (pinfunction "1_1") (pintype "passive"))
    )
    (net (code "39") (name "Net-(J12-Pad1)") (class "Default")
      (node (ref "J12") (pin "1") (pinfunction "1_1") (pintype "passive"))
      (node (ref "P11") (pin "2") (pinfunction "2_2") (pintype "passive"))
      (node (ref "R25") (pin "2") (pinfunction "2_2") (pintype "passive"))
    )
    (net (code "40") (name "Net-(J14-Pad1)") (class "Default")
      (node (ref "J14") (pin "1") (pinfunction "1_1") (pintype "passive"))
      (node (ref "P13") (pin "1") (pinfunction "1_1") (pintype "passive"))
      (node (ref "R26") (pin "2") (pinfunction "2_2") (pintype "passive"))
    )
    (net (code "41") (name "Net-(LED5-Pad2)") (class "Default")
      (node (ref "LED5") (pin "2") (pinfunction "2_2") (pintype "passive"))
      (node (ref "R69") (pin "2") (pinfunction "2_2") (pintype "passive"))
    )
    (net (code "42") (name "Net-(P15-Pad2)") (class "Default")
      (node (ref "P15") (pin "2") (pinfunction "2_2") (pintype "passive"))
      (node (ref "R33") (pin "1") (pinfunction "1_1") (pintype "passive"))
    )
    (net (code "43") (name "Net-(P17-Pad1)") (class "Default")
      (node (ref "P17") (pin "1") (pinfunction "1_1") (pintype "passive"))
      (node (ref "R34") (pin "1") (pinfunction "1_1") (pintype "passive"))
    )
    (net (code "44") (name "Net-(R22-Pad2)") (class "Default")
      (node (ref "R22") (pin "2") (pinfunction "2_2") (pintype "passive"))
      (node (ref "R23") (pin "1") (pinfunction "1_1") (pintype "passive"))
    )
    (net (code "45") (name "Net-(R23-Pad2)") (class "Default")
      (node (ref "R23") (pin "2") (pinfunction "2_2") (pintype "passive"))
      (node (ref "R24") (pin "1") (pinfunction "1_1") (pintype "passive"))
    )
    (net (code "46") (name "Net-(R27-Pad2)") (class "Default")
      (node (ref "R27") (pin "2") (pinfunction "2_2") (pintype "passive"))
      (node (ref "R28") (pin "1") (pinfunction "1_1") (pintype "passive"))
    )
    (net (code "47") (name "Net-(R28-Pad2)") (class "Default")
      (node (ref "R28") (pin "2") (pinfunction "2_2") (pintype "passive"))
      (node (ref "R29") (pin "1") (pinfunction "1_1") (pintype "passive"))
    )
    (net (code "48") (name "Net-(U5-IN+)") (class "Default")
      (node (ref "P5") (pin "1") (pinfunction "1_1") (pintype "passive"))
      (node (ref "U5") (pin "3") (pinfunction "IN+_3") (pintype "input"))
    )
    (net (code "49") (name "Net-(U5-IN-)") (class "Default")
      (node (ref "P4") (pin "2") (pinfunction "2_2") (pintype "passive"))
      (node (ref "U5") (pin "2") (pinfunction "IN-_2") (pintype "input"))
      (node (ref "U5") (pin "6") (pinfunction "OUT_6") (pintype "output"))
    )
    (net (code "50") (name "Net-(U6-IN+)") (class "Default")
      (node (ref "P6") (pin "2") (pinfunction "2_2") (pintype "passive"))
      (node (ref "U6") (pin "3") (pinfunction "IN+_3") (pintype "input"))
    )
    (net (code "51") (name "Net-(U6-IN-)") (class "Default")
      (node (ref "J11") (pin "1") (pinfunction "1_1") (pintype "passive"))
      (node (ref "P10") (pin "2") (pinfunction "2_2") (pintype "passive"))
      (node (ref "R21") (pin "2") (pinfunction "2_2") (pintype "passive"))
      (node (ref "U6") (pin "2") (pinfunction "IN-_2") (pintype "input"))
      (node (ref "U8") (pin "4") (pinfunction "VOUT+_4") (pintype "output"))
    )
    (net (code "52") (name "Net-(U6-OUT)") (class "Default")
      (node (ref "R17") (pin "1") (pinfunction "1_1") (pintype "passive"))
      (node (ref "U6") (pin "6") (pinfunction "OUT_6") (pintype "output"))
    )
    (net (code "53") (name "Net-(U6-V-)") (class "Default")
      (node (ref "R76") (pin "2") (pinfunction "2_2") (pintype "passive"))
      (node (ref "U6") (pin "4") (pinfunction "V-_4") (pintype "power_in"))
    )
    (net (code "54") (name "Net-(U7-EP)") (class "Default")
      (node (ref "R19") (pin "2") (pinfunction "2_2") (pintype "passive"))
      (node (ref "R20") (pin "2") (pinfunction "2_2") (pintype "passive"))
      (node (ref "U7") (pin "15") (pinfunction "EP_15") (pintype "power_in"))
    )
    (net (code "55") (name "Net-(U7-IN+)") (class "Default")
      (node (ref "P8") (pin "2") (pinfunction "2_2") (pintype "passive"))
      (node (ref "U7") (pin "8") (pinfunction "IN+_8") (pintype "input"))
    )
    (net (code "56") (name "Net-(U7-IN-)") (class "Default")
      (node (ref "P9") (pin "1") (pinfunction "1_1") (pintype "passive"))
      (node (ref "U7") (pin "9") (pinfunction "IN-_9") (pintype "input"))
    )
    (net (code "57") (name "Net-(U8-V-)") (class "Default")
      (node (ref "R77") (pin "1") (pinfunction "1_1") (pintype "passive"))
      (node (ref "R79") (pin "2") (pinfunction "2_2") (pintype "passive"))
      (node (ref "U8") (pin "6") (pinfunction "V-_6") (pintype "power_in"))
    )
    (net (code "58") (name "Net-(U8-VIN+)") (class "Default")
      (node (ref "R16") (pin "1") (pinfunction "1_1") (pintype "passive"))
      (node (ref "R17") (pin "2") (pinfunction "2_2") (pintype "passive"))
      (node (ref "U8") (pin "8") (pinfunction "VIN+_8") (pintype "input"))
    )
    (net (code "59") (name "Net-(U8-VIN-)") (class "Default")
      (node (ref "R18") (pin "2") (pinfunction "2_2") (pintype "passive"))
      (node (ref "R21") (pin "1") (pinfunction "1_1") (pintype "passive"))
      (node (ref "U8") (pin "1") (pinfunction "VIN-_1") (pintype "input"))
    )
    (net (code "60") (name "Net-(U8-VOUT-)") (class "Default")
      (node (ref "J8") (pin "1") (pinfunction "1_1") (pintype "passive"))
      (node (ref "P7") (pin "1") (pinfunction "1_1") (pintype "passive"))
      (node (ref "R16") (pin "2") (pinfunction "2_2") (pintype "passive"))
      (node (ref "U8") (pin "5") (pinfunction "VOUT-_5") (pintype "output"))
    )
    (net (code "61") (name "Net-(U9-V-)") (class "Default")
      (node (ref "R74") (pin "2") (pinfunction "2_2") (pintype "passive"))
      (node (ref "R75") (pin "1") (pinfunction "1_1") (pintype "passive"))
      (node (ref "U9") (pin "6") (pinfunction "V-_6") (pintype "power_in"))
    )
    (net (code "62") (name "Net-(U9-VIN+)") (class "Default")
      (node (ref "R26") (pin "1") (pinfunction "1_1") (pintype "passive"))
      (node (ref "R27") (pin "1") (pinfunction "1_1") (pintype "passive"))
      (node (ref "U9") (pin "8") (pinfunction "VIN+_8") (pintype "input"))
    )
    (net (code "63") (name "Net-(U9-VIN-)") (class "Default")
      (node (ref "R22") (pin "1") (pinfunction "1_1") (pintype "passive"))
      (node (ref "R25") (pin "1") (pinfunction "1_1") (pintype "passive"))
      (node (ref "U9") (pin "1") (pinfunction "VIN-_1") (pintype "input"))
    )
    (net (code "64") (name "Net-(U9-VOCM)") (class "Default")
      (node (ref "R73") (pin "1") (pinfunction "1_1") (pintype "passive"))
      (node (ref "U9") (pin "2") (pinfunction "VOCM_2") (pintype "input"))
    )
    (net (code "65") (name "Net-(U9-VOUT+)") (class "Default")
      (node (ref "P12") (pin "1") (pinfunction "1_1") (pintype "passive"))
      (node (ref "R24") (pin "2") (pinfunction "2_2") (pintype "passive"))
      (node (ref "U9") (pin "4") (pinfunction "VOUT+_4") (pintype "output"))
    )
    (net (code "66") (name "Net-(U9-VOUT-)") (class "Default")
      (node (ref "P14") (pin "2") (pinfunction "2_2") (pintype "passive"))
      (node (ref "R29") (pin "2") (pinfunction "2_2") (pintype "passive"))
      (node (ref "U9") (pin "5") (pinfunction "VOUT-_5") (pintype "output"))
    )
    (net (code "67") (name "Net-(U10-V-)") (class "Default")
      (node (ref "R71") (pin "1") (pinfunction "1_1") (pintype "passive"))
      (node (ref "R72") (pin "2") (pinfunction "2_2") (pintype "passive"))
      (node (ref "U10") (pin "6") (pinfunction "V-_6") (pintype "power_in"))
    )
    (net (code "68") (name "V5") (class "Default")
      (node (ref "C25") (pin "1") (pinfunction "Anode_1") (pintype "passive"))
      (node (ref "C31") (pin "1") (pinfunction "Anode_1") (pintype "passive"))
      (node (ref "C32") (pin "1") (pinfunction "Anode_1") (pintype "passive"))
      (node (ref "C33") (pin "1") (pinfunction "Anode_1") (pintype "passive"))
      (node (ref "C34") (pin "1") (pinfunction "Anode_1") (pintype "passive"))
      (node (ref "C35") (pin "1") (pinfunction "Anode_1") (pintype "passive"))
      (node (ref "C36") (pin "1") (pinfunction "Anode_1") (pintype "passive"))
      (node (ref "C39") (pin "1") (pinfunction "Anode_1") (pintype "passive"))
      (node (ref "C40") (pin "1") (pinfunction "Anode_1") (pintype "passive"))
      (node (ref "C42") (pin "1") (pinfunction "Anode_1") (pintype "passive"))
      (node (ref "C43") (pin "1") (pinfunction "Anode_1") (pintype "passive"))
      (node (ref "C56") (pin "1") (pinfunction "Anode_1") (pintype "passive"))
      (node (ref "C57") (pin "2") (pinfunction "Cathode_2") (pintype "passive"))
      (node (ref "SW4") (pin "1") (pinfunction "1_1") (pintype "passive"))
      (node (ref "U10") (pin "3") (pinfunction "V+_3") (pintype "power_in"))
      (node (ref "U10") (pin "7") (pinfunction "ENABLE_7") (pintype "input"))
      (node (ref "U5") (pin "7") (pinfunction "V+_7") (pintype "power_in"))
      (node (ref "U6") (pin "7") (pinfunction "V+_7") (pintype "power_in"))
      (node (ref "U7") (pin "14") (pinfunction "AVCC_14") (pintype "power_in"))
      (node (ref "U8") (pin "3") (pinfunction "V+_3") (pintype "power_in"))
      (node (ref "U8") (pin "7") (pinfunction "ENABLE_7") (pintype "input"))
      (node (ref "U9") (pin "3") (pinfunction "V+_3") (pintype "power_in"))
    )
    (net (code "69") (name "unconnected-(R78-Pad2)") (class "Default")
      (node (ref "R78") (pin "2") (pinfunction "2_2") (pintype "passive"))
    )
    (net (code "70") (name "unconnected-(U5-NC-Pad5)") (class "Default")
      (node (ref "U5") (pin "5") (pinfunction "NC_5") (pintype "passive+no_connect"))
    )
    (net (code "71") (name "unconnected-(U5-TRIM-Pad1)") (class "Default")
      (node (ref "U5") (pin "1") (pinfunction "TRIM_1") (pintype "input+no_connect"))
    )
    (net (code "72") (name "unconnected-(U5-TRIM-Pad8)") (class "Default")
      (node (ref "U5") (pin "8") (pinfunction "TRIM_8") (pintype "input+no_connect"))
    )
    (net (code "73") (name "unconnected-(U6-NC-Pad5)") (class "Default")
      (node (ref "U6") (pin "5") (pinfunction "NC_5") (pintype "passive+no_connect"))
    )
    (net (code "74") (name "unconnected-(U6-TRIM-Pad1)") (class "Default")
      (node (ref "U6") (pin "1") (pinfunction "TRIM_1") (pintype "input+no_connect"))
    )
    (net (code "75") (name "unconnected-(U6-TRIM-Pad8)") (class "Default")
      (node (ref "U6") (pin "8") (pinfunction "TRIM_8") (pintype "input+no_connect"))
    )
    (net (code "76") (name "unconnected-(U7-NC-Pad10)") (class "Default")
      (node (ref "U7") (pin "10") (pinfunction "NC_10") (pintype "passive+no_connect"))
    )
  )
)
